# Pg03__AM335X_Section_2.net
KiCad netlist of a schematic drawn in Altium Designer
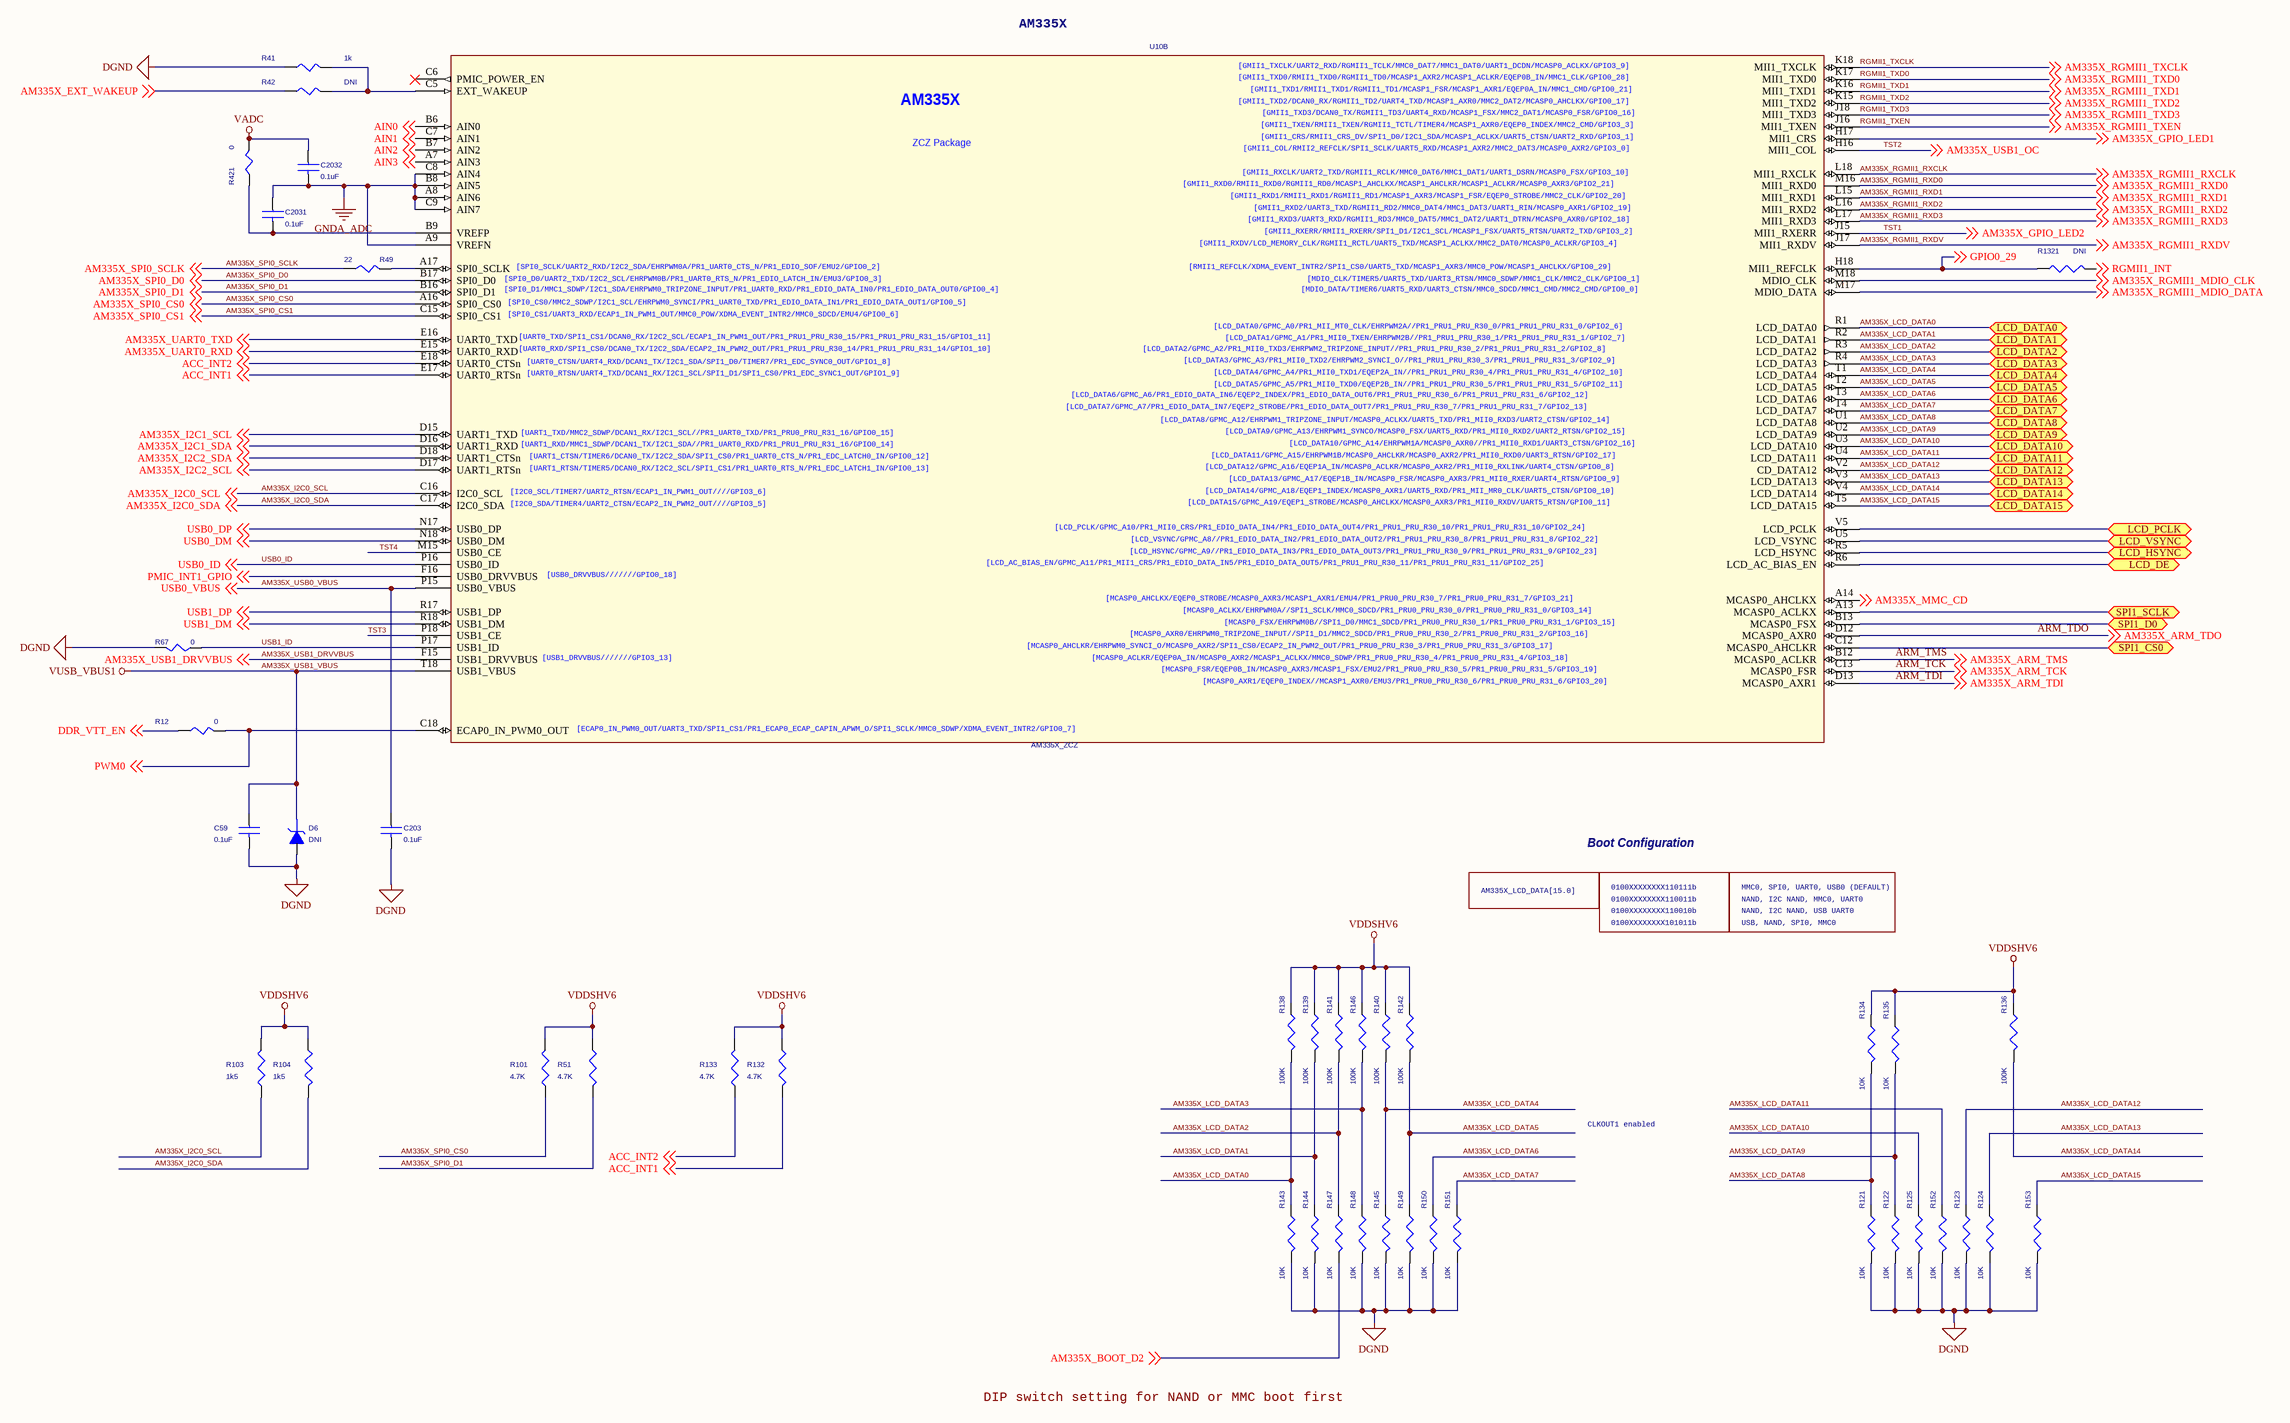
[diagram p0: Pg03_ AM335X Section 2 .SchDoc]

(export (version "E")
  (design (tool "Eeschema 10.0.6"))
  (components
    (comp (ref "C59")
      (value "0.1uF")
      (footprint "SM-7351-CAP-0402")
      (fields (field (name "TIINTPARTNUMBER") "1C0089") (field (name "MFR") "Kemet"))
      (libsource (lib "*") (part "0.1uFCapacitor16V10%0402_Dup1"))
    )
    (comp (ref "C203")
      (value "0.1uF")
      (footprint "SM-7351-CAP-0402")
      (fields (field (name "TIINTPARTNUMBER") "1C0089") (field (name "MFR") "Kemet"))
      (libsource (lib "*") (part "0.1uFCapacitor16V10%0402_Dup1"))
    )
    (comp (ref "C2031")
      (value "0.1uF")
      (footprint "SM-7351-CAP-0402")
      (fields (field (name "TIINTPARTNUMBER") "1C0089") (field (name "MFR") "Kemet"))
      (libsource (lib "*") (part "0.1uFCapacitor16V10%0402_Dup1"))
    )
    (comp (ref "C2032")
      (value "0.1uF")
      (footprint "SM-7351-CAP-0402")
      (fields (field (name "TIINTPARTNUMBER") "1C0089") (field (name "MFR") "Kemet"))
      (libsource (lib "*") (part "0.1uFCapacitor16V10%0402_Dup1"))
    )
    (comp (ref "D6")
      (value "DNI")
      (footprint "GMD2_2pin")
      (description "Voltage Surpressor 15.0V")
      (fields (field (name "MFR") "Rohm") (field (name "TIINTPARTNUMBER") "1E0020"))
      (libsource (lib "*") (part "Diode_Zener_5.1V_100mW"))
    )
    (comp (ref "R12")
      (value "0")
      (footprint "SM-7351-RES-0402")
      (fields (field (name "MFR") "Panasonic") (field (name "TIINTPARTNUMBER") "1R0098"))
      (libsource (lib "*") (part "ZeroOhmResistor1/16W0402"))
    )
    (comp (ref "R41")
      (value "1k")
      (footprint "SM-7351-RES-0402")
      (description "Resistor Zero ohm Jumper 0402")
      (fields (field (name "MFR") "Panasonic") (field (name "TIINTPARTNUMBER") "1R0098"))
      (libsource (lib "*") (part "ZeroOhmResistor1/16W0402_Dup2"))
    )
    (comp (ref "R42")
      (value "DNI")
      (footprint "SM-7351-RES-0402")
      (description "Resistor Zero ohm Jumper 0402")
      (fields (field (name "MFR") "Panasonic") (field (name "TIINTPARTNUMBER") "1R0098"))
      (libsource (lib "*") (part "ZeroOhmResistor1/16W0402_Dup2"))
    )
    (comp (ref "R49")
      (value "22")
      (footprint "SM-7351-RES-0402")
      (description "Resistor 22 ohm 1/16W 1% 0402")
      (fields (field (name "MFR") "ROHM") (field (name "TIINTPARTNUMBER") "1R0175"))
      (libsource (lib "*") (part "22OhmResistor1/16W1%0402"))
    )
    (comp (ref "R51")
      (value "4.7K")
      (footprint "SM-7351-RES-0402")
      (description "Resistor 4.7Kohm 1/16W 5% 0402")
      (fields (field (name "TIINTPARTNUMBER") "1R0183") (field (name "MFR") "Stackpole Electronics"))
      (libsource (lib "*") (part "4.7KOhmResistor1/16W0402_Dup1"))
    )
    (comp (ref "R67")
      (value "0")
      (footprint "SM-7351-RES-0402")
      (description "Resistor Zero ohm Jumper 0402")
      (fields (field (name "TIINTPARTNUMBER") "1R0098") (field (name "MFR") "Panasonic"))
      (libsource (lib "*") (part "ZeroOhmResistor1/16W0402_Dup4"))
    )
    (comp (ref "R101")
      (value "4.7K")
      (footprint "SM-7351-RES-0402")
      (description "Resistor 4.7Kohm 1/16W 5% 0402")
      (fields (field (name "TIINTPARTNUMBER") "1R0183") (field (name "MFR") "Stackpole Electronics"))
      (libsource (lib "*") (part "4.7KOhmResistor1/16W0402_Dup1"))
    )
    (comp (ref "R103")
      (value "1k5")
      (footprint "SM-7351-RES-0402")
      (description "Resistor 4.7Kohm 1/16W 5% 0402")
      (fields (field (name "TIINTPARTNUMBER") "1R0183") (field (name "MFR") "Stackpole Electronics"))
      (libsource (lib "*") (part "4.7KOhmResistor1/16W0402_Dup1"))
    )
    (comp (ref "R104")
      (value "1k5")
      (footprint "SM-7351-RES-0402")
      (description "Resistor 4.7Kohm 1/16W 5% 0402")
      (fields (field (name "TIINTPARTNUMBER") "1R0183") (field (name "MFR") "Stackpole Electronics"))
      (libsource (lib "*") (part "4.7KOhmResistor1/16W0402_Dup1"))
    )
    (comp (ref "R121")
      (value "10K")
      (footprint "SM-7351-RES-0402")
      (description "Resistor 10Kohm 1/16W 5% 0402")
      (fields (field (name "TIINTPARTNUMBER") "1R0168") (field (name "MFR") "Rohm"))
      (libsource (lib "*") (part "10KOhmResistor1/16W0402_Dup1"))
    )
    (comp (ref "R122")
      (value "10K")
      (footprint "SM-7351-RES-0402")
      (description "Resistor 10Kohm 1/16W 5% 0402")
      (fields (field (name "TIINTPARTNUMBER") "1R0168") (field (name "MFR") "Rohm"))
      (libsource (lib "*") (part "10KOhmResistor1/16W0402_Dup1"))
    )
    (comp (ref "R123")
      (value "10K")
      (footprint "SM-7351-RES-0402")
      (description "Resistor 10Kohm 1/16W 5% 0402")
      (fields (field (name "TIINTPARTNUMBER") "1R0168") (field (name "MFR") "Rohm"))
      (libsource (lib "*") (part "10KOhmResistor1/16W0402_Dup1"))
    )
    (comp (ref "R124")
      (value "10K")
      (footprint "SM-7351-RES-0402")
      (description "Resistor 10Kohm 1/16W 5% 0402")
      (fields (field (name "TIINTPARTNUMBER") "1R0168") (field (name "MFR") "Rohm"))
      (libsource (lib "*") (part "10KOhmResistor1/16W0402_Dup1"))
    )
    (comp (ref "R125")
      (value "10K")
      (footprint "SM-7351-RES-0402")
      (description "Resistor 10Kohm 1/16W 5% 0402")
      (fields (field (name "TIINTPARTNUMBER") "1R0168") (field (name "MFR") "Rohm"))
      (libsource (lib "*") (part "10KOhmResistor1/16W0402_Dup1"))
    )
    (comp (ref "R132")
      (value "4.7K")
      (footprint "SM-7351-RES-0402")
      (description "Resistor 4.7Kohm 1/16W 5% 0402")
      (fields (field (name "TIINTPARTNUMBER") "1R0183") (field (name "MFR") "Stackpole Electronics"))
      (libsource (lib "*") (part "4.7KOhmResistor1/16W0402_Dup1"))
    )
    (comp (ref "R133")
      (value "4.7K")
      (footprint "SM-7351-RES-0402")
      (description "Resistor 4.7Kohm 1/16W 5% 0402")
      (fields (field (name "TIINTPARTNUMBER") "1R0183") (field (name "MFR") "Stackpole Electronics"))
      (libsource (lib "*") (part "4.7KOhmResistor1/16W0402_Dup1"))
    )
    (comp (ref "R134")
      (value "10K")
      (footprint "SM-7351-RES-0402")
      (description "Resistor 10Kohm 1/16W 5% 0402")
      (fields (field (name "TIINTPARTNUMBER") "1R0168") (field (name "MFR") "Rohm"))
      (libsource (lib "*") (part "10KOhmResistor1/16W0402_Dup1"))
    )
    (comp (ref "R135")
      (value "10K")
      (footprint "SM-7351-RES-0402")
      (description "Resistor 10Kohm 1/16W 5% 0402")
      (fields (field (name "TIINTPARTNUMBER") "1R0168") (field (name "MFR") "Rohm"))
      (libsource (lib "*") (part "10KOhmResistor1/16W0402_Dup1"))
    )
    (comp (ref "R136")
      (value "100K")
      (footprint "SM-7351-RES-0402")
      (fields (field (name "TIINTPARTNUMBER") "1R0181") (field (name "MFR") "Stackpole Electronics"))
      (libsource (lib "*") (part "100KOhmResistor1/16W0402_Dup1"))
    )
    (comp (ref "R138")
      (value "100K")
      (footprint "SM-7351-RES-0402")
      (fields (field (name "TIINTPARTNUMBER") "1R0181") (field (name "MFR") "Stackpole Electronics"))
      (libsource (lib "*") (part "100KOhmResistor1/16W0402_Dup1"))
    )
    (comp (ref "R139")
      (value "100K")
      (footprint "SM-7351-RES-0402")
      (fields (field (name "TIINTPARTNUMBER") "1R0181") (field (name "MFR") "Stackpole Electronics"))
      (libsource (lib "*") (part "100KOhmResistor1/16W0402_Dup1"))
    )
    (comp (ref "R140")
      (value "100K")
      (footprint "SM-7351-RES-0402")
      (fields (field (name "TIINTPARTNUMBER") "1R0181") (field (name "MFR") "Stackpole Electronics"))
      (libsource (lib "*") (part "100KOhmResistor1/16W0402_Dup1"))
    )
    (comp (ref "R141")
      (value "100K")
      (footprint "SM-7351-RES-0402")
      (fields (field (name "TIINTPARTNUMBER") "1R0181") (field (name "MFR") "Stackpole Electronics"))
      (libsource (lib "*") (part "100KOhmResistor1/16W0402_Dup1"))
    )
    (comp (ref "R142")
      (value "100K")
      (footprint "SM-7351-RES-0402")
      (fields (field (name "TIINTPARTNUMBER") "1R0181") (field (name "MFR") "Stackpole Electronics"))
      (libsource (lib "*") (part "100KOhmResistor1/16W0402_Dup1"))
    )
    (comp (ref "R143")
      (value "10K")
      (footprint "SM-7351-RES-0402")
      (description "Resistor 10Kohm 1/16W 5% 0402")
      (fields (field (name "TIINTPARTNUMBER") "1R0168") (field (name "MFR") "Rohm"))
      (libsource (lib "*") (part "10KOhmResistor1/16W0402_Dup1"))
    )
    (comp (ref "R144")
      (value "10K")
      (footprint "SM-7351-RES-0402")
      (description "Resistor 10Kohm 1/16W 5% 0402")
      (fields (field (name "TIINTPARTNUMBER") "1R0168") (field (name "MFR") "Rohm"))
      (libsource (lib "*") (part "10KOhmResistor1/16W0402_Dup1"))
    )
    (comp (ref "R145")
      (value "10K")
      (footprint "SM-7351-RES-0402")
      (description "Resistor 10Kohm 1/16W 5% 0402")
      (fields (field (name "TIINTPARTNUMBER") "1R0168") (field (name "MFR") "Rohm"))
      (libsource (lib "*") (part "10KOhmResistor1/16W0402_Dup1"))
    )
    (comp (ref "R146")
      (value "100K")
      (footprint "SM-7351-RES-0402")
      (fields (field (name "TIINTPARTNUMBER") "1R0181") (field (name "MFR") "Stackpole Electronics"))
      (libsource (lib "*") (part "100KOhmResistor1/16W0402_Dup1"))
    )
    (comp (ref "R147")
      (value "10K")
      (footprint "SM-7351-RES-0402")
      (description "Resistor 10Kohm 1/16W 5% 0402")
      (fields (field (name "TIINTPARTNUMBER") "1R0168") (field (name "MFR") "Rohm"))
      (libsource (lib "*") (part "10KOhmResistor1/16W0402_Dup1"))
    )
    (comp (ref "R148")
      (value "10K")
      (footprint "SM-7351-RES-0402")
      (description "Resistor 10Kohm 1/16W 5% 0402")
      (fields (field (name "TIINTPARTNUMBER") "1R0168") (field (name "MFR") "Rohm"))
      (libsource (lib "*") (part "10KOhmResistor1/16W0402_Dup1"))
    )
    (comp (ref "R149")
      (value "10K")
      (footprint "SM-7351-RES-0402")
      (description "Resistor 10Kohm 1/16W 5% 0402")
      (fields (field (name "TIINTPARTNUMBER") "1R0168") (field (name "MFR") "Rohm"))
      (libsource (lib "*") (part "10KOhmResistor1/16W0402_Dup1"))
    )
    (comp (ref "R150")
      (value "10K")
      (footprint "SM-7351-RES-0402")
      (description "Resistor 10Kohm 1/16W 5% 0402")
      (fields (field (name "TIINTPARTNUMBER") "1R0168") (field (name "MFR") "Rohm"))
      (libsource (lib "*") (part "10KOhmResistor1/16W0402_Dup1"))
    )
    (comp (ref "R151")
      (value "10K")
      (footprint "SM-7351-RES-0402")
      (description "Resistor 10Kohm 1/16W 5% 0402")
      (fields (field (name "TIINTPARTNUMBER") "1R0168") (field (name "MFR") "Rohm"))
      (libsource (lib "*") (part "10KOhmResistor1/16W0402_Dup1"))
    )
    (comp (ref "R152")
      (value "10K")
      (footprint "SM-7351-RES-0402")
      (description "Resistor 10Kohm 1/16W 5% 0402")
      (fields (field (name "TIINTPARTNUMBER") "1R0168") (field (name "MFR") "Rohm"))
      (libsource (lib "*") (part "10KOhmResistor1/16W0402_Dup1"))
    )
    (comp (ref "R153")
      (value "10K")
      (footprint "SM-7351-RES-0402")
      (description "Resistor 10Kohm 1/16W 5% 0402")
      (fields (field (name "TIINTPARTNUMBER") "1R0168") (field (name "MFR") "Rohm"))
      (libsource (lib "*") (part "10KOhmResistor1/16W0402_Dup1"))
    )
    (comp (ref "R421")
      (value "0")
      (footprint "SM-7351-RES-0402")
      (description "Resistor Zero ohm Jumper 0402")
      (fields (field (name "MFR") "Panasonic") (field (name "TIINTPARTNUMBER") "1R0098"))
      (libsource (lib "*") (part "ZeroOhmResistor1/16W0402_Dup2"))
    )
    (comp (ref "R1321")
      (value "DNI")
      (footprint "SM-7351-RES-0402")
      (description "Resistor 4.7Kohm 1/16W 5% 0402")
      (fields (field (name "TIINTPARTNUMBER") "1R0183") (field (name "MFR") "Stackpole Electronics"))
      (libsource (lib "*") (part "4.7KOhmResistor1/16W0402_Dup1"))
    )
    (comp (ref "U10")
      (value "AM335X_ZCZ")
      (footprint "BGA15X15-324-55M")
      (fields (field (name "TIINTPARTNUMBER") "1A0242") (field (name "MFR") "TI"))
      (libsource (lib "*") (part "AM335X_15mmx15mm"))
    )
  )
  (nets
    (net (code "1") (name "/AM335X_LCD_DATA0") (class "Default")
      (node (ref "R138") (pin "1") (pinfunction "P1_1") (pintype "passive"))
      (node (ref "R143") (pin "2") (pinfunction "P2_2") (pintype "passive"))
      (node (ref "U10") (pin "R1") (pinfunction "LCD_DATA0_R1") (pintype "output"))
    )
    (net (code "2") (name "/AM335X_LCD_DATA1") (class "Default")
      (node (ref "R139") (pin "1") (pinfunction "P1_1") (pintype "passive"))
      (node (ref "R144") (pin "2") (pinfunction "P2_2") (pintype "passive"))
      (node (ref "U10") (pin "R2") (pinfunction "LCD_DATA1_R2") (pintype "output"))
    )
    (net (code "3") (name "/AM335X_LCD_DATA2") (class "Default")
      (node (ref "R141") (pin "1") (pinfunction "P1_1") (pintype "passive"))
      (node (ref "R147") (pin "2") (pinfunction "P2_2") (pintype "passive"))
      (node (ref "U10") (pin "R3") (pinfunction "LCD_DATA2_R3") (pintype "output"))
    )
    (net (code "4") (name "/AM335X_LCD_DATA3") (class "Default")
      (node (ref "R146") (pin "1") (pinfunction "P1_1") (pintype "passive"))
      (node (ref "R148") (pin "2") (pinfunction "P2_2") (pintype "passive"))
      (node (ref "U10") (pin "R4") (pinfunction "LCD_DATA3_R4") (pintype "output"))
    )
    (net (code "5") (name "/AM335X_LCD_DATA4") (class "Default")
      (node (ref "R140") (pin "1") (pinfunction "P1_1") (pintype "passive"))
      (node (ref "R145") (pin "2") (pinfunction "P2_2") (pintype "passive"))
      (node (ref "U10") (pin "T1") (pinfunction "LCD_DATA4_T1") (pintype "bidirectional"))
    )
    (net (code "6") (name "/AM335X_LCD_DATA5") (class "Default")
      (node (ref "R142") (pin "1") (pinfunction "P1_1") (pintype "passive"))
      (node (ref "R149") (pin "2") (pinfunction "P2_2") (pintype "passive"))
      (node (ref "U10") (pin "T2") (pinfunction "LCD_DATA5_T2") (pintype "bidirectional"))
    )
    (net (code "7") (name "/AM335X_LCD_DATA6") (class "Default")
      (node (ref "R150") (pin "2") (pinfunction "P2_2") (pintype "passive"))
      (node (ref "U10") (pin "T3") (pinfunction "LCD_DATA6_T3") (pintype "bidirectional"))
    )
    (net (code "8") (name "/AM335X_LCD_DATA7") (class "Default")
      (node (ref "R151") (pin "2") (pinfunction "P2_2") (pintype "passive"))
      (node (ref "U10") (pin "T4") (pinfunction "LCD_DATA7_T4") (pintype "bidirectional"))
    )
    (net (code "9") (name "/AM335X_LCD_DATA8") (class "Default")
      (node (ref "R121") (pin "2") (pinfunction "P2_2") (pintype "passive"))
      (node (ref "R134") (pin "1") (pinfunction "P1_1") (pintype "passive"))
      (node (ref "U10") (pin "U1") (pinfunction "LCD_DATA8_U1") (pintype "bidirectional"))
    )
    (net (code "10") (name "/AM335X_LCD_DATA9") (class "Default")
      (node (ref "R122") (pin "2") (pinfunction "P2_2") (pintype "passive"))
      (node (ref "R135") (pin "1") (pinfunction "P1_1") (pintype "passive"))
      (node (ref "U10") (pin "U2") (pinfunction "LCD_DATA9_U2") (pintype "bidirectional"))
    )
    (net (code "11") (name "/AM335X_LCD_DATA10") (class "Default")
      (node (ref "R125") (pin "2") (pinfunction "P2_2") (pintype "passive"))
      (node (ref "U10") (pin "U3") (pinfunction "LCD_DATA10_U3") (pintype "bidirectional"))
    )
    (net (code "12") (name "/AM335X_LCD_DATA11") (class "Default")
      (node (ref "R152") (pin "2") (pinfunction "P2_2") (pintype "passive"))
      (node (ref "U10") (pin "U4") (pinfunction "LCD_DATA11_U4") (pintype "bidirectional"))
    )
    (net (code "13") (name "/AM335X_LCD_DATA12") (class "Default")
      (node (ref "R123") (pin "2") (pinfunction "P2_2") (pintype "passive"))
      (node (ref "U10") (pin "V2") (pinfunction "CD_DATA12_V2") (pintype "bidirectional"))
    )
    (net (code "14") (name "/AM335X_LCD_DATA13") (class "Default")
      (node (ref "R124") (pin "2") (pinfunction "P2_2") (pintype "passive"))
      (node (ref "U10") (pin "V3") (pinfunction "LCD_DATA13_V3") (pintype "bidirectional"))
    )
    (net (code "15") (name "/AM335X_LCD_DATA14") (class "Default")
      (node (ref "R136") (pin "1") (pinfunction "P1_1") (pintype "passive"))
      (node (ref "U10") (pin "V4") (pinfunction "LCD_DATA14_V4") (pintype "bidirectional"))
    )
    (net (code "16") (name "/AM335X_LCD_DATA15") (class "Default")
      (node (ref "R153") (pin "2") (pinfunction "P2_2") (pintype "passive"))
      (node (ref "U10") (pin "T5") (pinfunction "LCD_DATA15_T5") (pintype "bidirectional"))
    )
    (net (code "17") (name "/LCD_DE") (class "Default")
      (node (ref "U10") (pin "R6") (pinfunction "LCD_AC_BIAS_EN_R6") (pintype "bidirectional"))
    )
    (net (code "18") (name "/LCD_HSYNC") (class "Default")
      (node (ref "U10") (pin "R5") (pinfunction "LCD_HSYNC_R5") (pintype "bidirectional"))
    )
    (net (code "19") (name "/LCD_PCLK") (class "Default")
      (node (ref "U10") (pin "V5") (pinfunction "LCD_PCLK_V5") (pintype "bidirectional"))
    )
    (net (code "20") (name "/LCD_VSYNC") (class "Default")
      (node (ref "U10") (pin "U5") (pinfunction "LCD_VSYNC_U5") (pintype "bidirectional"))
    )
    (net (code "21") (name "/SPI1_CS0") (class "Default")
      (node (ref "U10") (pin "C12") (pinfunction "MCASP0_AHCLKR_C12") (pintype "bidirectional"))
    )
    (net (code "22") (name "/SPI1_D0") (class "Default")
      (node (ref "U10") (pin "B13") (pinfunction "MCASP0_FSX_B13") (pintype "bidirectional"))
    )
    (net (code "23") (name "/SPI1_SCLK") (class "Default")
      (node (ref "U10") (pin "A13") (pinfunction "MCASP0_ACLKX_A13") (pintype "bidirectional"))
    )
    (net (code "24") (name "/TST3") (class "Default")
      (node (ref "U10") (pin "P18") (pinfunction "USB1_CE_P18") (pintype "passive"))
    )
    (net (code "25") (name "/TST4") (class "Default")
      (node (ref "U10") (pin "M15") (pinfunction "USB0_CE_M15") (pintype "passive"))
    )
    (net (code "26") (name "/USB1_ID") (class "Default")
      (node (ref "R67") (pin "2") (pinfunction "P2_2") (pintype "passive"))
      (node (ref "U10") (pin "P17") (pinfunction "USB1_ID_P17") (pintype "passive"))
    )
    (net (code "27") (name "ACC_INT1") (class "Default")
      (node (ref "R132") (pin "1") (pinfunction "P1_1") (pintype "passive"))
      (node (ref "U10") (pin "E17") (pinfunction "UART0_RTSn_E17") (pintype "bidirectional"))
    )
    (net (code "28") (name "ACC_INT2") (class "Default")
      (node (ref "R133") (pin "1") (pinfunction "P1_1") (pintype "passive"))
      (node (ref "U10") (pin "E18") (pinfunction "UART0_CTSn_E18") (pintype "bidirectional"))
    )
    (net (code "29") (name "AIN0") (class "Default")
      (node (ref "U10") (pin "B6") (pinfunction "AIN0_B6") (pintype "input"))
    )
    (net (code "30") (name "AIN1") (class "Default")
      (node (ref "U10") (pin "C7") (pinfunction "AIN1_C7") (pintype "input"))
    )
    (net (code "31") (name "AIN2") (class "Default")
      (node (ref "U10") (pin "B7") (pinfunction "AIN2_B7") (pintype "input"))
    )
    (net (code "32") (name "AIN3") (class "Default")
      (node (ref "U10") (pin "A7") (pinfunction "AIN3_A7") (pintype "input"))
    )
    (net (code "33") (name "AM335X_ARM_TCK") (class "Default")
      (node (ref "U10") (pin "C13") (pinfunction "MCASP0_FSR_C13") (pintype "bidirectional"))
    )
    (net (code "34") (name "AM335X_ARM_TDI") (class "Default")
      (node (ref "U10") (pin "D13") (pinfunction "MCASP0_AXR1_D13") (pintype "bidirectional"))
    )
    (net (code "35") (name "AM335X_ARM_TDO") (class "Default")
      (node (ref "U10") (pin "D12") (pinfunction "MCASP0_AXR0_D12") (pintype "bidirectional"))
    )
    (net (code "36") (name "AM335X_ARM_TMS") (class "Default")
      (node (ref "U10") (pin "B12") (pinfunction "MCASP0_ACLKR_B12") (pintype "bidirectional"))
    )
    (net (code "37") (name "AM335X_BOOT_D2") (class "Default")
      (node (ref "R147") (pin "1") (pinfunction "P1_1") (pintype "passive"))
    )
    (net (code "38") (name "AM335X_EXT_WAKEUP") (class "Default")
      (node (ref "R42") (pin "2") (pinfunction "P2_2") (pintype "passive"))
    )
    (net (code "39") (name "AM335X_GPIO_LED1") (class "Default")
      (node (ref "U10") (pin "H17") (pinfunction "MII1_CRS_H17") (pintype "bidirectional"))
    )
    (net (code "40") (name "AM335X_GPIO_LED2") (class "Default")
      (node (ref "U10") (pin "J15") (pinfunction "MII1_RXERR_J15") (pintype "bidirectional"))
    )
    (net (code "41") (name "AM335X_I2C0_SCL") (class "Default")
      (node (ref "R103") (pin "1") (pinfunction "P1_1") (pintype "passive"))
      (node (ref "U10") (pin "C16") (pinfunction "I2C0_SCL_C16") (pintype "bidirectional"))
    )
    (net (code "42") (name "AM335X_I2C0_SDA") (class "Default")
      (node (ref "R104") (pin "1") (pinfunction "P1_1") (pintype "passive"))
      (node (ref "U10") (pin "C17") (pinfunction "I2C0_SDA_C17") (pintype "bidirectional"))
    )
    (net (code "43") (name "AM335X_I2C1_SCL") (class "Default")
      (node (ref "U10") (pin "D15") (pinfunction "UART1_TXD_D15") (pintype "bidirectional"))
    )
    (net (code "44") (name "AM335X_I2C1_SDA") (class "Default")
      (node (ref "U10") (pin "D16") (pinfunction "UART1_RXD_D16") (pintype "bidirectional"))
    )
    (net (code "45") (name "AM335X_I2C2_SCL") (class "Default")
      (node (ref "U10") (pin "D17") (pinfunction "UART1_RTSn_D17") (pintype "bidirectional"))
    )
    (net (code "46") (name "AM335X_I2C2_SDA") (class "Default")
      (node (ref "U10") (pin "D18") (pinfunction "UART1_CTSn_D18") (pintype "bidirectional"))
    )
    (net (code "47") (name "AM335X_MMC_CD") (class "Default")
      (node (ref "U10") (pin "A14") (pinfunction "MCASP0_AHCLKX_A14") (pintype "bidirectional"))
    )
    (net (code "48") (name "AM335X_RGMII1_MDIO_CLK") (class "Default")
      (node (ref "U10") (pin "M18") (pinfunction "MDIO_CLK_M18") (pintype "bidirectional"))
    )
    (net (code "49") (name "AM335X_RGMII1_MDIO_DATA") (class "Default")
      (node (ref "U10") (pin "M17") (pinfunction "MDIO_DATA_M17") (pintype "bidirectional"))
    )
    (net (code "50") (name "AM335X_RGMII1_RXCLK") (class "Default")
      (node (ref "U10") (pin "L18") (pinfunction "MII1_RXCLK_L18") (pintype "bidirectional"))
    )
    (net (code "51") (name "AM335X_RGMII1_RXD0") (class "Default")
      (node (ref "U10") (pin "M16") (pinfunction "MII1_RXD0_M16") (pintype "passive"))
    )
    (net (code "52") (name "AM335X_RGMII1_RXD1") (class "Default")
      (node (ref "U10") (pin "L15") (pinfunction "MII1_RXD1_L15") (pintype "bidirectional"))
    )
    (net (code "53") (name "AM335X_RGMII1_RXD2") (class "Default")
      (node (ref "U10") (pin "L16") (pinfunction "MII1_RXD2_L16") (pintype "bidirectional"))
    )
    (net (code "54") (name "AM335X_RGMII1_RXD3") (class "Default")
      (node (ref "U10") (pin "L17") (pinfunction "MII1_RXD3_L17") (pintype "bidirectional"))
    )
    (net (code "55") (name "AM335X_RGMII1_RXDV") (class "Default")
      (node (ref "U10") (pin "J17") (pinfunction "MII1_RXDV_J17") (pintype "bidirectional"))
    )
    (net (code "56") (name "AM335X_RGMII1_TXCLK") (class "Default")
      (node (ref "U10") (pin "K18") (pinfunction "MII1_TXCLK_K18") (pintype "bidirectional"))
    )
    (net (code "57") (name "AM335X_RGMII1_TXD0") (class "Default")
      (node (ref "U10") (pin "K17") (pinfunction "MII1_TXD0_K17") (pintype "bidirectional"))
    )
    (net (code "58") (name "AM335X_RGMII1_TXD1") (class "Default")
      (node (ref "U10") (pin "K16") (pinfunction "MII1_TXD1_K16") (pintype "bidirectional"))
    )
    (net (code "59") (name "AM335X_RGMII1_TXD2") (class "Default")
      (node (ref "U10") (pin "K15") (pinfunction "MII1_TXD2_K15") (pintype "bidirectional"))
    )
    (net (code "60") (name "AM335X_RGMII1_TXD3") (class "Default")
      (node (ref "U10") (pin "J18") (pinfunction "MII1_TXD3_J18") (pintype "bidirectional"))
    )
    (net (code "61") (name "AM335X_RGMII1_TXEN") (class "Default")
      (node (ref "U10") (pin "J16") (pinfunction "MII1_TXEN_J16") (pintype "bidirectional"))
    )
    (net (code "62") (name "AM335X_SPI0_CS0") (class "Default")
      (node (ref "R101") (pin "1") (pinfunction "P1_1") (pintype "passive"))
      (node (ref "U10") (pin "A16") (pinfunction "SPI0_CS0_A16") (pintype "bidirectional"))
    )
    (net (code "63") (name "AM335X_SPI0_CS1") (class "Default")
      (node (ref "U10") (pin "C15") (pinfunction "SPI0_CS1_C15") (pintype "bidirectional"))
    )
    (net (code "64") (name "AM335X_SPI0_D0") (class "Default")
      (node (ref "U10") (pin "B17") (pinfunction "SPI0_D0_B17") (pintype "bidirectional"))
    )
    (net (code "65") (name "AM335X_SPI0_D1") (class "Default")
      (node (ref "R51") (pin "1") (pinfunction "P1_1") (pintype "passive"))
      (node (ref "U10") (pin "B16") (pinfunction "SPI0_D1_B16") (pintype "bidirectional"))
    )
    (net (code "66") (name "AM335X_SPI0_SCLK") (class "Default")
      (node (ref "R49") (pin "2") (pinfunction "P2_2") (pintype "passive"))
    )
    (net (code "67") (name "AM335X_UART0_RXD") (class "Default")
      (node (ref "U10") (pin "E15") (pinfunction "UART0_RXD_E15") (pintype "bidirectional"))
    )
    (net (code "68") (name "AM335X_UART0_TXD") (class "Default")
      (node (ref "U10") (pin "E16") (pinfunction "UART0_TXD_E16") (pintype "bidirectional"))
    )
    (net (code "69") (name "AM335X_USB1_DRVVBUS") (class "Default")
      (node (ref "U10") (pin "F15") (pinfunction "USB1_DRVVBUS_F15") (pintype "passive"))
    )
    (net (code "70") (name "AM335X_USB1_OC") (class "Default")
      (node (ref "U10") (pin "H16") (pinfunction "MII1_COL_H16") (pintype "bidirectional"))
    )
    (net (code "71") (name "DDR_VTT_EN") (class "Default")
      (node (ref "R12") (pin "2") (pinfunction "P2_2") (pintype "passive"))
    )
    (net (code "72") (name "DGND") (class "Default")
      (node (ref "C203") (pin "2") (pinfunction "2_2") (pintype "passive"))
      (node (ref "C59") (pin "2") (pinfunction "2_2") (pintype "passive"))
      (node (ref "D6") (pin "2") (pinfunction "ANODE_2") (pintype "passive"))
      (node (ref "R121") (pin "1") (pinfunction "P1_1") (pintype "passive"))
      (node (ref "R122") (pin "1") (pinfunction "P1_1") (pintype "passive"))
      (node (ref "R123") (pin "1") (pinfunction "P1_1") (pintype "passive"))
      (node (ref "R124") (pin "1") (pinfunction "P1_1") (pintype "passive"))
      (node (ref "R125") (pin "1") (pinfunction "P1_1") (pintype "passive"))
      (node (ref "R143") (pin "1") (pinfunction "P1_1") (pintype "passive"))
      (node (ref "R144") (pin "1") (pinfunction "P1_1") (pintype "passive"))
      (node (ref "R145") (pin "1") (pinfunction "P1_1") (pintype "passive"))
      (node (ref "R148") (pin "1") (pinfunction "P1_1") (pintype "passive"))
      (node (ref "R149") (pin "1") (pinfunction "P1_1") (pintype "passive"))
      (node (ref "R150") (pin "1") (pinfunction "P1_1") (pintype "passive"))
      (node (ref "R151") (pin "1") (pinfunction "P1_1") (pintype "passive"))
      (node (ref "R152") (pin "1") (pinfunction "P1_1") (pintype "passive"))
      (node (ref "R153") (pin "1") (pinfunction "P1_1") (pintype "passive"))
      (node (ref "R41") (pin "2") (pinfunction "P2_2") (pintype "passive"))
      (node (ref "R67") (pin "1") (pinfunction "P1_1") (pintype "passive"))
    )
    (net (code "73") (name "GNDA_ADC") (class "Default")
      (node (ref "C2031") (pin "1") (pinfunction "1_1") (pintype "passive"))
      (node (ref "C2032") (pin "2") (pinfunction "2_2") (pintype "passive"))
      (node (ref "U10") (pin "A8") (pinfunction "AIN6_A8") (pintype "input"))
      (node (ref "U10") (pin "A9") (pinfunction "VREFN_A9") (pintype "passive"))
      (node (ref "U10") (pin "B8") (pinfunction "AIN5_B8") (pintype "input"))
      (node (ref "U10") (pin "C8") (pinfunction "AIN4_C8") (pintype "input"))
      (node (ref "U10") (pin "C9") (pinfunction "AIN7_C9") (pintype "input"))
    )
    (net (code "74") (name "GPIO0_29") (class "Default")
      (node (ref "R1321") (pin "2") (pinfunction "P2_2") (pintype "passive"))
      (node (ref "U10") (pin "H18") (pinfunction "MII1_REFCLK_H18") (pintype "bidirectional"))
    )
    (net (code "75") (name "Net-(R41-P1)") (class "Default")
      (node (ref "R41") (pin "1") (pinfunction "P1_1") (pintype "passive"))
      (node (ref "R42") (pin "1") (pinfunction "P1_1") (pintype "passive"))
      (node (ref "U10") (pin "C5") (pinfunction "EXT_WAKEUP_C5") (pintype "input"))
    )
    (net (code "76") (name "Net-(R49-P1)") (class "Default")
      (node (ref "R49") (pin "1") (pinfunction "P1_1") (pintype "passive"))
      (node (ref "U10") (pin "A17") (pinfunction "SPI0_SCLK_A17") (pintype "bidirectional"))
    )
    (net (code "77") (name "Net-(R421-P2)") (class "Default")
      (node (ref "C2031") (pin "2") (pinfunction "2_2") (pintype "passive"))
      (node (ref "R421") (pin "2") (pinfunction "P2_2") (pintype "passive"))
      (node (ref "U10") (pin "B9") (pinfunction "VREFP_B9") (pintype "passive"))
    )
    (net (code "78") (name "PMIC_INT1_GPIO") (class "Default")
      (node (ref "U10") (pin "F16") (pinfunction "USB0_DRVVBUS_F16") (pintype "passive"))
    )
    (net (code "79") (name "PWM0") (class "Default")
      (node (ref "R12") (pin "1") (pinfunction "P1_1") (pintype "passive"))
      (node (ref "U10") (pin "C18") (pinfunction "ECAP0_IN_PWM0_OUT_C18") (pintype "bidirectional"))
    )
    (net (code "80") (name "RGMII1_INT") (class "Default")
      (node (ref "R1321") (pin "1") (pinfunction "P1_1") (pintype "passive"))
    )
    (net (code "81") (name "USB0_DM") (class "Default")
      (node (ref "U10") (pin "N18") (pinfunction "USB0_DM_N18") (pintype "bidirectional"))
    )
    (net (code "82") (name "USB0_DP") (class "Default")
      (node (ref "U10") (pin "N17") (pinfunction "USB0_DP_N17") (pintype "bidirectional"))
    )
    (net (code "83") (name "USB0_ID") (class "Default")
      (node (ref "U10") (pin "P16") (pinfunction "USB0_ID_P16") (pintype "passive"))
    )
    (net (code "84") (name "USB0_VBUS") (class "Default")
      (node (ref "C203") (pin "1") (pinfunction "1_1") (pintype "passive"))
      (node (ref "U10") (pin "P15") (pinfunction "USB0_VBUS_P15") (pintype "passive"))
    )
    (net (code "85") (name "USB1_DM") (class "Default")
      (node (ref "U10") (pin "R18") (pinfunction "USB1_DM_R18") (pintype "bidirectional"))
    )
    (net (code "86") (name "USB1_DP") (class "Default")
      (node (ref "U10") (pin "R17") (pinfunction "USB1_DP_R17") (pintype "bidirectional"))
    )
    (net (code "87") (name "VADC") (class "Default")
      (node (ref "C2032") (pin "1") (pinfunction "1_1") (pintype "passive"))
      (node (ref "R421") (pin "1") (pinfunction "P1_1") (pintype "passive"))
    )
    (net (code "88") (name "VDDSHV6") (class "Default")
      (node (ref "R101") (pin "2") (pinfunction "P2_2") (pintype "passive"))
      (node (ref "R103") (pin "2") (pinfunction "P2_2") (pintype "passive"))
      (node (ref "R104") (pin "2") (pinfunction "P2_2") (pintype "passive"))
      (node (ref "R132") (pin "2") (pinfunction "P2_2") (pintype "passive"))
      (node (ref "R133") (pin "2") (pinfunction "P2_2") (pintype "passive"))
      (node (ref "R134") (pin "2") (pinfunction "P2_2") (pintype "passive"))
      (node (ref "R135") (pin "2") (pinfunction "P2_2") (pintype "passive"))
      (node (ref "R136") (pin "2") (pinfunction "P2_2") (pintype "passive"))
      (node (ref "R138") (pin "2") (pinfunction "P2_2") (pintype "passive"))
      (node (ref "R139") (pin "2") (pinfunction "P2_2") (pintype "passive"))
      (node (ref "R140") (pin "2") (pinfunction "P2_2") (pintype "passive"))
      (node (ref "R141") (pin "2") (pinfunction "P2_2") (pintype "passive"))
      (node (ref "R142") (pin "2") (pinfunction "P2_2") (pintype "passive"))
      (node (ref "R146") (pin "2") (pinfunction "P2_2") (pintype "passive"))
      (node (ref "R51") (pin "2") (pinfunction "P2_2") (pintype "passive"))
    )
    (net (code "89") (name "VUSB_VBUS1") (class "Default")
      (node (ref "C59") (pin "1") (pinfunction "1_1") (pintype "passive"))
      (node (ref "D6") (pin "1") (pinfunction "CATHODE_1") (pintype "passive"))
      (node (ref "U10") (pin "T18") (pinfunction "USB1_VBUS_T18") (pintype "passive"))
    )
    (net (code "90") (name "unconnected-(U10B-PMIC_POWER_EN-PadC6)") (class "Default")
      (node (ref "U10") (pin "C6") (pinfunction "PMIC_POWER_EN_C6") (pintype "output+no_connect"))
    )
  )
)
